# ultimate_Co-Op_v1_2.net
KiCad netlist of a schematic drawn in EAGLE
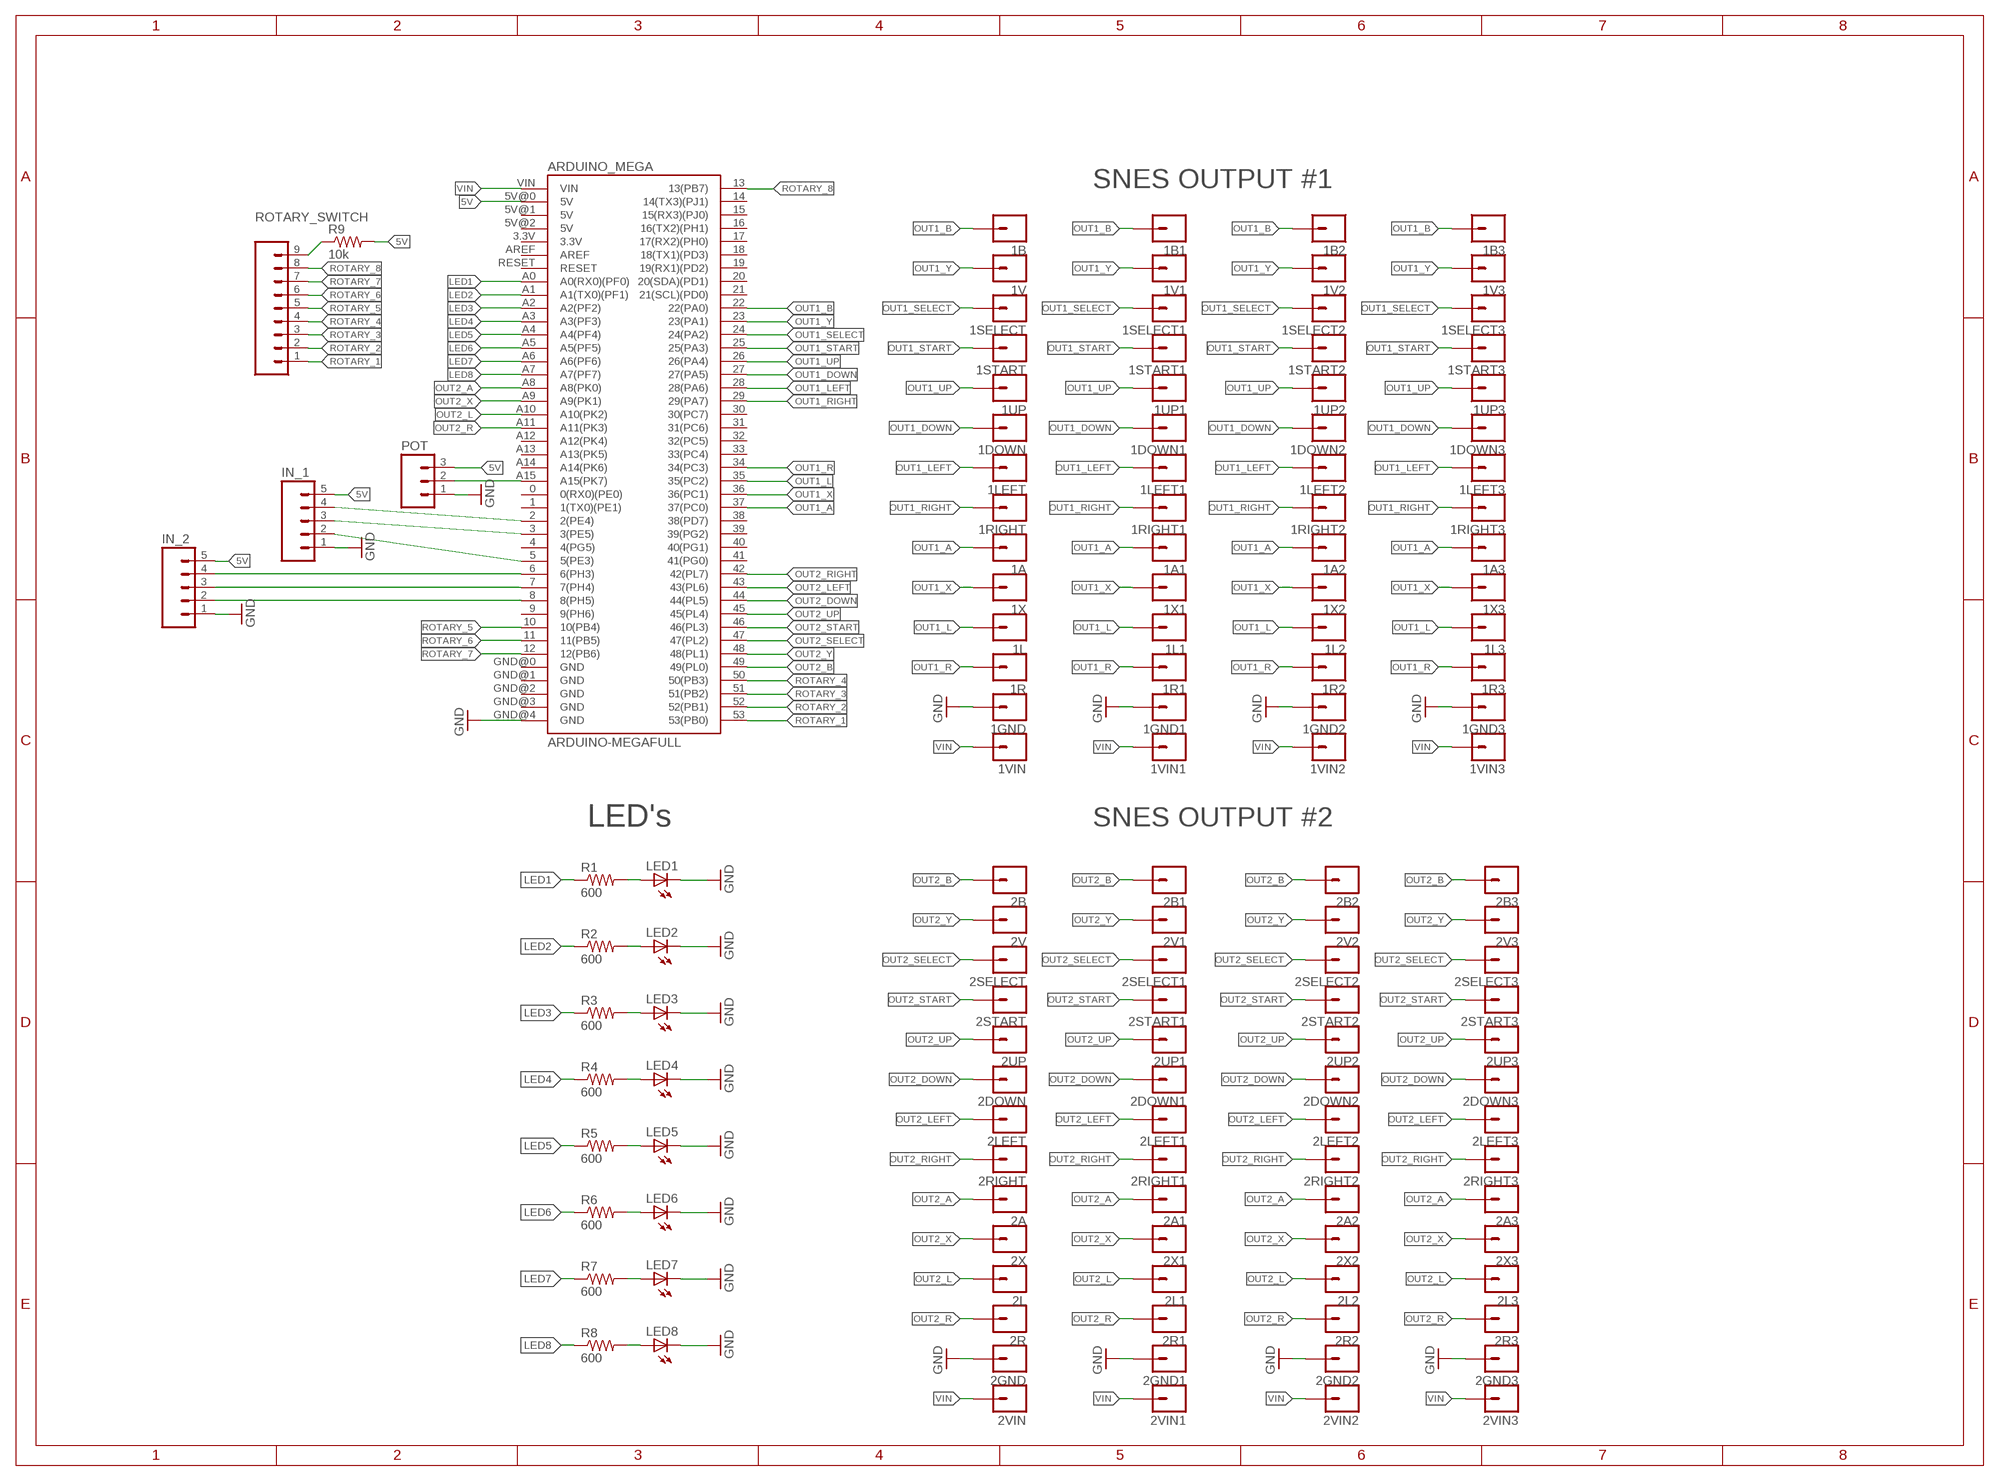
[diagram p0: schematic, sheet 1]

(export (version "E")
  (design (tool "Eeschema 10.0.6"))
  (components
    (comp (ref "1A")
      (value "M01PTH")
      (footprint "eagle-import:1X01")
      (libsource (lib "eagle-import") (part "M01PTH"))
    )
    (comp (ref "1A1")
      (value "M01PTH")
      (footprint "eagle-import:1X01")
      (libsource (lib "eagle-import") (part "M01PTH"))
    )
    (comp (ref "1A2")
      (value "M01PTH")
      (footprint "eagle-import:1X01")
      (libsource (lib "eagle-import") (part "M01PTH"))
    )
    (comp (ref "1A3")
      (value "M01PTH")
      (footprint "eagle-import:1X01")
      (libsource (lib "eagle-import") (part "M01PTH"))
    )
    (comp (ref "1B")
      (value "M01PTH")
      (footprint "eagle-import:1X01")
      (libsource (lib "eagle-import") (part "M01PTH"))
    )
    (comp (ref "1B1")
      (value "M01PTH")
      (footprint "eagle-import:1X01")
      (libsource (lib "eagle-import") (part "M01PTH"))
    )
    (comp (ref "1B2")
      (value "M01PTH")
      (footprint "eagle-import:1X01")
      (libsource (lib "eagle-import") (part "M01PTH"))
    )
    (comp (ref "1B3")
      (value "M01PTH")
      (footprint "eagle-import:1X01")
      (libsource (lib "eagle-import") (part "M01PTH"))
    )
    (comp (ref "1DOWN")
      (value "M01PTH")
      (footprint "eagle-import:1X01")
      (libsource (lib "eagle-import") (part "M01PTH"))
    )
    (comp (ref "1DOWN1")
      (value "M01PTH")
      (footprint "eagle-import:1X01")
      (libsource (lib "eagle-import") (part "M01PTH"))
    )
    (comp (ref "1DOWN2")
      (value "M01PTH")
      (footprint "eagle-import:1X01")
      (libsource (lib "eagle-import") (part "M01PTH"))
    )
    (comp (ref "1DOWN3")
      (value "M01PTH")
      (footprint "eagle-import:1X01")
      (libsource (lib "eagle-import") (part "M01PTH"))
    )
    (comp (ref "1GND")
      (value "M01PTH")
      (footprint "eagle-import:1X01")
      (libsource (lib "eagle-import") (part "M01PTH"))
    )
    (comp (ref "1GND1")
      (value "M01PTH")
      (footprint "eagle-import:1X01")
      (libsource (lib "eagle-import") (part "M01PTH"))
    )
    (comp (ref "1GND2")
      (value "M01PTH")
      (footprint "eagle-import:1X01")
      (libsource (lib "eagle-import") (part "M01PTH"))
    )
    (comp (ref "1GND3")
      (value "M01PTH")
      (footprint "eagle-import:1X01")
      (libsource (lib "eagle-import") (part "M01PTH"))
    )
    (comp (ref "1L")
      (value "M01PTH")
      (footprint "eagle-import:1X01")
      (libsource (lib "eagle-import") (part "M01PTH"))
    )
    (comp (ref "1L1")
      (value "M01PTH")
      (footprint "eagle-import:1X01")
      (libsource (lib "eagle-import") (part "M01PTH"))
    )
    (comp (ref "1L2")
      (value "M01PTH")
      (footprint "eagle-import:1X01")
      (libsource (lib "eagle-import") (part "M01PTH"))
    )
    (comp (ref "1L3")
      (value "M01PTH")
      (footprint "eagle-import:1X01")
      (libsource (lib "eagle-import") (part "M01PTH"))
    )
    (comp (ref "1LEFT")
      (value "M01PTH")
      (footprint "eagle-import:1X01")
      (libsource (lib "eagle-import") (part "M01PTH"))
    )
    (comp (ref "1LEFT1")
      (value "M01PTH")
      (footprint "eagle-import:1X01")
      (libsource (lib "eagle-import") (part "M01PTH"))
    )
    (comp (ref "1LEFT2")
      (value "M01PTH")
      (footprint "eagle-import:1X01")
      (libsource (lib "eagle-import") (part "M01PTH"))
    )
    (comp (ref "1LEFT3")
      (value "M01PTH")
      (footprint "eagle-import:1X01")
      (libsource (lib "eagle-import") (part "M01PTH"))
    )
    (comp (ref "1R")
      (value "M01PTH")
      (footprint "eagle-import:1X01")
      (libsource (lib "eagle-import") (part "M01PTH"))
    )
    (comp (ref "1R1")
      (value "M01PTH")
      (footprint "eagle-import:1X01")
      (libsource (lib "eagle-import") (part "M01PTH"))
    )
    (comp (ref "1R2")
      (value "M01PTH")
      (footprint "eagle-import:1X01")
      (libsource (lib "eagle-import") (part "M01PTH"))
    )
    (comp (ref "1R3")
      (value "M01PTH")
      (footprint "eagle-import:1X01")
      (libsource (lib "eagle-import") (part "M01PTH"))
    )
    (comp (ref "1RIGHT")
      (value "M01PTH")
      (footprint "eagle-import:1X01")
      (libsource (lib "eagle-import") (part "M01PTH"))
    )
    (comp (ref "1RIGHT1")
      (value "M01PTH")
      (footprint "eagle-import:1X01")
      (libsource (lib "eagle-import") (part "M01PTH"))
    )
    (comp (ref "1RIGHT2")
      (value "M01PTH")
      (footprint "eagle-import:1X01")
      (libsource (lib "eagle-import") (part "M01PTH"))
    )
    (comp (ref "1RIGHT3")
      (value "M01PTH")
      (footprint "eagle-import:1X01")
      (libsource (lib "eagle-import") (part "M01PTH"))
    )
    (comp (ref "1SELECT")
      (value "M01PTH")
      (footprint "eagle-import:1X01")
      (libsource (lib "eagle-import") (part "M01PTH"))
    )
    (comp (ref "1SELECT1")
      (value "M01PTH")
      (footprint "eagle-import:1X01")
      (libsource (lib "eagle-import") (part "M01PTH"))
    )
    (comp (ref "1SELECT2")
      (value "M01PTH")
      (footprint "eagle-import:1X01")
      (libsource (lib "eagle-import") (part "M01PTH"))
    )
    (comp (ref "1SELECT3")
      (value "M01PTH")
      (footprint "eagle-import:1X01")
      (libsource (lib "eagle-import") (part "M01PTH"))
    )
    (comp (ref "1START")
      (value "M01PTH")
      (footprint "eagle-import:1X01")
      (libsource (lib "eagle-import") (part "M01PTH"))
    )
    (comp (ref "1START1")
      (value "M01PTH")
      (footprint "eagle-import:1X01")
      (libsource (lib "eagle-import") (part "M01PTH"))
    )
    (comp (ref "1START2")
      (value "M01PTH")
      (footprint "eagle-import:1X01")
      (libsource (lib "eagle-import") (part "M01PTH"))
    )
    (comp (ref "1START3")
      (value "M01PTH")
      (footprint "eagle-import:1X01")
      (libsource (lib "eagle-import") (part "M01PTH"))
    )
    (comp (ref "1UP")
      (value "M01PTH")
      (footprint "eagle-import:1X01")
      (libsource (lib "eagle-import") (part "M01PTH"))
    )
    (comp (ref "1UP1")
      (value "M01PTH")
      (footprint "eagle-import:1X01")
      (libsource (lib "eagle-import") (part "M01PTH"))
    )
    (comp (ref "1UP2")
      (value "M01PTH")
      (footprint "eagle-import:1X01")
      (libsource (lib "eagle-import") (part "M01PTH"))
    )
    (comp (ref "1UP3")
      (value "M01PTH")
      (footprint "eagle-import:1X01")
      (libsource (lib "eagle-import") (part "M01PTH"))
    )
    (comp (ref "1V")
      (value "M01PTH")
      (footprint "eagle-import:1X01")
      (libsource (lib "eagle-import") (part "M01PTH"))
    )
    (comp (ref "1V1")
      (value "M01PTH")
      (footprint "eagle-import:1X01")
      (libsource (lib "eagle-import") (part "M01PTH"))
    )
    (comp (ref "1V2")
      (value "M01PTH")
      (footprint "eagle-import:1X01")
      (libsource (lib "eagle-import") (part "M01PTH"))
    )
    (comp (ref "1V3")
      (value "M01PTH")
      (footprint "eagle-import:1X01")
      (libsource (lib "eagle-import") (part "M01PTH"))
    )
    (comp (ref "1VIN")
      (value "M01PTH")
      (footprint "eagle-import:1X01")
      (libsource (lib "eagle-import") (part "M01PTH"))
    )
    (comp (ref "1VIN1")
      (value "M01PTH")
      (footprint "eagle-import:1X01")
      (libsource (lib "eagle-import") (part "M01PTH"))
    )
    (comp (ref "1VIN2")
      (value "M01PTH")
      (footprint "eagle-import:1X01")
      (libsource (lib "eagle-import") (part "M01PTH"))
    )
    (comp (ref "1VIN3")
      (value "M01PTH")
      (footprint "eagle-import:1X01")
      (libsource (lib "eagle-import") (part "M01PTH"))
    )
    (comp (ref "1X")
      (value "M01PTH")
      (footprint "eagle-import:1X01")
      (libsource (lib "eagle-import") (part "M01PTH"))
    )
    (comp (ref "1X1")
      (value "M01PTH")
      (footprint "eagle-import:1X01")
      (libsource (lib "eagle-import") (part "M01PTH"))
    )
    (comp (ref "1X2")
      (value "M01PTH")
      (footprint "eagle-import:1X01")
      (libsource (lib "eagle-import") (part "M01PTH"))
    )
    (comp (ref "1X3")
      (value "M01PTH")
      (footprint "eagle-import:1X01")
      (libsource (lib "eagle-import") (part "M01PTH"))
    )
    (comp (ref "2A")
      (value "M01PTH")
      (footprint "eagle-import:1X01")
      (libsource (lib "eagle-import") (part "M01PTH"))
    )
    (comp (ref "2A1")
      (value "M01PTH")
      (footprint "eagle-import:1X01")
      (libsource (lib "eagle-import") (part "M01PTH"))
    )
    (comp (ref "2A2")
      (value "M01PTH")
      (footprint "eagle-import:1X01")
      (libsource (lib "eagle-import") (part "M01PTH"))
    )
    (comp (ref "2A3")
      (value "M01PTH")
      (footprint "eagle-import:1X01")
      (libsource (lib "eagle-import") (part "M01PTH"))
    )
    (comp (ref "2B")
      (value "M01PTH")
      (footprint "eagle-import:1X01")
      (libsource (lib "eagle-import") (part "M01PTH"))
    )
    (comp (ref "2B1")
      (value "M01PTH")
      (footprint "eagle-import:1X01")
      (libsource (lib "eagle-import") (part "M01PTH"))
    )
    (comp (ref "2B2")
      (value "M01PTH")
      (footprint "eagle-import:1X01")
      (libsource (lib "eagle-import") (part "M01PTH"))
    )
    (comp (ref "2B3")
      (value "M01PTH")
      (footprint "eagle-import:1X01")
      (libsource (lib "eagle-import") (part "M01PTH"))
    )
    (comp (ref "2DOWN")
      (value "M01PTH")
      (footprint "eagle-import:1X01")
      (libsource (lib "eagle-import") (part "M01PTH"))
    )
    (comp (ref "2DOWN1")
      (value "M01PTH")
      (footprint "eagle-import:1X01")
      (libsource (lib "eagle-import") (part "M01PTH"))
    )
    (comp (ref "2DOWN2")
      (value "M01PTH")
      (footprint "eagle-import:1X01")
      (libsource (lib "eagle-import") (part "M01PTH"))
    )
    (comp (ref "2DOWN3")
      (value "M01PTH")
      (footprint "eagle-import:1X01")
      (libsource (lib "eagle-import") (part "M01PTH"))
    )
    (comp (ref "2GND")
      (value "M01PTH")
      (footprint "eagle-import:1X01")
      (libsource (lib "eagle-import") (part "M01PTH"))
    )
    (comp (ref "2GND1")
      (value "M01PTH")
      (footprint "eagle-import:1X01")
      (libsource (lib "eagle-import") (part "M01PTH"))
    )
    (comp (ref "2GND2")
      (value "M01PTH")
      (footprint "eagle-import:1X01")
      (libsource (lib "eagle-import") (part "M01PTH"))
    )
    (comp (ref "2GND3")
      (value "M01PTH")
      (footprint "eagle-import:1X01")
      (libsource (lib "eagle-import") (part "M01PTH"))
    )
    (comp (ref "2L")
      (value "M01PTH")
      (footprint "eagle-import:1X01")
      (libsource (lib "eagle-import") (part "M01PTH"))
    )
    (comp (ref "2L1")
      (value "M01PTH")
      (footprint "eagle-import:1X01")
      (libsource (lib "eagle-import") (part "M01PTH"))
    )
    (comp (ref "2L2")
      (value "M01PTH")
      (footprint "eagle-import:1X01")
      (libsource (lib "eagle-import") (part "M01PTH"))
    )
    (comp (ref "2L3")
      (value "M01PTH")
      (footprint "eagle-import:1X01")
      (libsource (lib "eagle-import") (part "M01PTH"))
    )
    (comp (ref "2LEFT")
      (value "M01PTH")
      (footprint "eagle-import:1X01")
      (libsource (lib "eagle-import") (part "M01PTH"))
    )
    (comp (ref "2LEFT1")
      (value "M01PTH")
      (footprint "eagle-import:1X01")
      (libsource (lib "eagle-import") (part "M01PTH"))
    )
    (comp (ref "2LEFT2")
      (value "M01PTH")
      (footprint "eagle-import:1X01")
      (libsource (lib "eagle-import") (part "M01PTH"))
    )
    (comp (ref "2LEFT3")
      (value "M01PTH")
      (footprint "eagle-import:1X01")
      (libsource (lib "eagle-import") (part "M01PTH"))
    )
    (comp (ref "2R")
      (value "M01PTH")
      (footprint "eagle-import:1X01")
      (libsource (lib "eagle-import") (part "M01PTH"))
    )
    (comp (ref "2R1")
      (value "M01PTH")
      (footprint "eagle-import:1X01")
      (libsource (lib "eagle-import") (part "M01PTH"))
    )
    (comp (ref "2R2")
      (value "M01PTH")
      (footprint "eagle-import:1X01")
      (libsource (lib "eagle-import") (part "M01PTH"))
    )
    (comp (ref "2R3")
      (value "M01PTH")
      (footprint "eagle-import:1X01")
      (libsource (lib "eagle-import") (part "M01PTH"))
    )
    (comp (ref "2RIGHT")
      (value "M01PTH")
      (footprint "eagle-import:1X01")
      (libsource (lib "eagle-import") (part "M01PTH"))
    )
    (comp (ref "2RIGHT1")
      (value "M01PTH")
      (footprint "eagle-import:1X01")
      (libsource (lib "eagle-import") (part "M01PTH"))
    )
    (comp (ref "2RIGHT2")
      (value "M01PTH")
      (footprint "eagle-import:1X01")
      (libsource (lib "eagle-import") (part "M01PTH"))
    )
    (comp (ref "2RIGHT3")
      (value "M01PTH")
      (footprint "eagle-import:1X01")
      (libsource (lib "eagle-import") (part "M01PTH"))
    )
    (comp (ref "2SELECT")
      (value "M01PTH")
      (footprint "eagle-import:1X01")
      (libsource (lib "eagle-import") (part "M01PTH"))
    )
    (comp (ref "2SELECT1")
      (value "M01PTH")
      (footprint "eagle-import:1X01")
      (libsource (lib "eagle-import") (part "M01PTH"))
    )
    (comp (ref "2SELECT2")
      (value "M01PTH")
      (footprint "eagle-import:1X01")
      (libsource (lib "eagle-import") (part "M01PTH"))
    )
    (comp (ref "2SELECT3")
      (value "M01PTH")
      (footprint "eagle-import:1X01")
      (libsource (lib "eagle-import") (part "M01PTH"))
    )
    (comp (ref "2START")
      (value "M01PTH")
      (footprint "eagle-import:1X01")
      (libsource (lib "eagle-import") (part "M01PTH"))
    )
    (comp (ref "2START1")
      (value "M01PTH")
      (footprint "eagle-import:1X01")
      (libsource (lib "eagle-import") (part "M01PTH"))
    )
    (comp (ref "2START2")
      (value "M01PTH")
      (footprint "eagle-import:1X01")
      (libsource (lib "eagle-import") (part "M01PTH"))
    )
    (comp (ref "2START3")
      (value "M01PTH")
      (footprint "eagle-import:1X01")
      (libsource (lib "eagle-import") (part "M01PTH"))
    )
    (comp (ref "2UP")
      (value "M01PTH")
      (footprint "eagle-import:1X01")
      (libsource (lib "eagle-import") (part "M01PTH"))
    )
    (comp (ref "2UP1")
      (value "M01PTH")
      (footprint "eagle-import:1X01")
      (libsource (lib "eagle-import") (part "M01PTH"))
    )
    (comp (ref "2UP2")
      (value "M01PTH")
      (footprint "eagle-import:1X01")
      (libsource (lib "eagle-import") (part "M01PTH"))
    )
    (comp (ref "2UP3")
      (value "M01PTH")
      (footprint "eagle-import:1X01")
      (libsource (lib "eagle-import") (part "M01PTH"))
    )
    (comp (ref "2V")
      (value "M01PTH")
      (footprint "eagle-import:1X01")
      (libsource (lib "eagle-import") (part "M01PTH"))
    )
    (comp (ref "2V1")
      (value "M01PTH")
      (footprint "eagle-import:1X01")
      (libsource (lib "eagle-import") (part "M01PTH"))
    )
    (comp (ref "2V2")
      (value "M01PTH")
      (footprint "eagle-import:1X01")
      (libsource (lib "eagle-import") (part "M01PTH"))
    )
    (comp (ref "2V3")
      (value "M01PTH")
      (footprint "eagle-import:1X01")
      (libsource (lib "eagle-import") (part "M01PTH"))
    )
    (comp (ref "2VIN")
      (value "M01PTH")
      (footprint "eagle-import:1X01")
      (libsource (lib "eagle-import") (part "M01PTH"))
    )
    (comp (ref "2VIN1")
      (value "M01PTH")
      (footprint "eagle-import:1X01")
      (libsource (lib "eagle-import") (part "M01PTH"))
    )
    (comp (ref "2VIN2")
      (value "M01PTH")
      (footprint "eagle-import:1X01")
      (libsource (lib "eagle-import") (part "M01PTH"))
    )
    (comp (ref "2VIN3")
      (value "M01PTH")
      (footprint "eagle-import:1X01")
      (libsource (lib "eagle-import") (part "M01PTH"))
    )
    (comp (ref "2X")
      (value "M01PTH")
      (footprint "eagle-import:1X01")
      (libsource (lib "eagle-import") (part "M01PTH"))
    )
    (comp (ref "2X1")
      (value "M01PTH")
      (footprint "eagle-import:1X01")
      (libsource (lib "eagle-import") (part "M01PTH"))
    )
    (comp (ref "2X2")
      (value "M01PTH")
      (footprint "eagle-import:1X01")
      (libsource (lib "eagle-import") (part "M01PTH"))
    )
    (comp (ref "2X3")
      (value "M01PTH")
      (footprint "eagle-import:1X01")
      (libsource (lib "eagle-import") (part "M01PTH"))
    )
    (comp (ref "ARDUINO_MEGA")
      (value "ARDUINO-MEGAFULL")
      (footprint "eagle-import:ARDUINO_MEGA")
      (libsource (lib "eagle-import") (part "ARDUINO-MEGAFULL"))
    )
    (comp (ref "IN_1")
      (value "M05PTH")
      (footprint "eagle-import:1X05")
      (libsource (lib "eagle-import") (part "M05PTH"))
    )
    (comp (ref "IN_2")
      (value "M05PTH")
      (footprint "eagle-import:1X05")
      (libsource (lib "eagle-import") (part "M05PTH"))
    )
    (comp (ref "LED1")
      (value "LED5MM")
      (footprint "eagle-import:LED5MM")
      (libsource (lib "eagle-import") (part "LED5MM"))
    )
    (comp (ref "LED2")
      (value "LED5MM")
      (footprint "eagle-import:LED5MM")
      (libsource (lib "eagle-import") (part "LED5MM"))
    )
    (comp (ref "LED3")
      (value "LED5MM")
      (footprint "eagle-import:LED5MM")
      (libsource (lib "eagle-import") (part "LED5MM"))
    )
    (comp (ref "LED4")
      (value "LED5MM")
      (footprint "eagle-import:LED5MM")
      (libsource (lib "eagle-import") (part "LED5MM"))
    )
    (comp (ref "LED5")
      (value "LED5MM")
      (footprint "eagle-import:LED5MM")
      (libsource (lib "eagle-import") (part "LED5MM"))
    )
    (comp (ref "LED6")
      (value "LED5MM")
      (footprint "eagle-import:LED5MM")
      (libsource (lib "eagle-import") (part "LED5MM"))
    )
    (comp (ref "LED7")
      (value "LED5MM")
      (footprint "eagle-import:LED5MM")
      (libsource (lib "eagle-import") (part "LED5MM"))
    )
    (comp (ref "LED8")
      (value "LED5MM")
      (footprint "eagle-import:LED5MM")
      (libsource (lib "eagle-import") (part "LED5MM"))
    )
    (comp (ref "POT")
      (value "M03LONGPADS")
      (footprint "eagle-import:1X03_LONGPADS")
      (libsource (lib "eagle-import") (part "M03LONGPADS"))
    )
    (comp (ref "R1")
      (value "600")
      (footprint "eagle-import:0204_7")
      (libsource (lib "eagle-import") (part "R-US_0204/7"))
    )
    (comp (ref "R2")
      (value "600")
      (footprint "eagle-import:0204_7")
      (libsource (lib "eagle-import") (part "R-US_0204/7"))
    )
    (comp (ref "R3")
      (value "600")
      (footprint "eagle-import:0204_7")
      (libsource (lib "eagle-import") (part "R-US_0204/7"))
    )
    (comp (ref "R4")
      (value "600")
      (footprint "eagle-import:0204_7")
      (libsource (lib "eagle-import") (part "R-US_0204/7"))
    )
    (comp (ref "R5")
      (value "600")
      (footprint "eagle-import:0204_7")
      (libsource (lib "eagle-import") (part "R-US_0204/7"))
    )
    (comp (ref "R6")
      (value "600")
      (footprint "eagle-import:0204_7")
      (libsource (lib "eagle-import") (part "R-US_0204/7"))
    )
    (comp (ref "R7")
      (value "600")
      (footprint "eagle-import:0204_7")
      (libsource (lib "eagle-import") (part "R-US_0204/7"))
    )
    (comp (ref "R8")
      (value "600")
      (footprint "eagle-import:0204_7")
      (libsource (lib "eagle-import") (part "R-US_0204/7"))
    )
    (comp (ref "R9")
      (value "10k")
      (footprint "eagle-import:0204_7")
      (libsource (lib "eagle-import") (part "R-US_0204/7"))
    )
    (comp (ref "ROTARY_SWITCH")
      (value "M09")
      (footprint "eagle-import:1X09")
      (libsource (lib "eagle-import") (part "M09"))
    )
  )
  (nets
    (net (code "1") (name "5V") (class "Default")
      (node (ref "ARDUINO_MEGA") (pin "5V@0") (pinfunction "5V_5V@0") (pintype "bidirectional"))
      (node (ref "IN_1") (pin "5") (pinfunction "5_5") (pintype "passive"))
      (node (ref "IN_2") (pin "5") (pinfunction "5_5") (pintype "passive"))
      (node (ref "POT") (pin "3") (pinfunction "3_3") (pintype "passive"))
      (node (ref "R9") (pin "2") (pinfunction "2_2") (pintype "passive"))
    )
    (net (code "2") (name "GND") (class "Default")
      (node (ref "1GND") (pin "1") (pinfunction "1_1") (pintype "passive"))
      (node (ref "1GND1") (pin "1") (pinfunction "1_1") (pintype "passive"))
      (node (ref "1GND2") (pin "1") (pinfunction "1_1") (pintype "passive"))
      (node (ref "1GND3") (pin "1") (pinfunction "1_1") (pintype "passive"))
      (node (ref "2GND") (pin "1") (pinfunction "1_1") (pintype "passive"))
      (node (ref "2GND1") (pin "1") (pinfunction "1_1") (pintype "passive"))
      (node (ref "2GND2") (pin "1") (pinfunction "1_1") (pintype "passive"))
      (node (ref "2GND3") (pin "1") (pinfunction "1_1") (pintype "passive"))
      (node (ref "ARDUINO_MEGA") (pin "GND@4") (pinfunction "GND_GND@4") (pintype "bidirectional"))
      (node (ref "IN_1") (pin "1") (pinfunction "1_1") (pintype "passive"))
      (node (ref "IN_2") (pin "1") (pinfunction "1_1") (pintype "passive"))
      (node (ref "LED1") (pin "K") (pinfunction "C_K") (pintype "passive"))
      (node (ref "LED2") (pin "K") (pinfunction "C_K") (pintype "passive"))
      (node (ref "LED3") (pin "K") (pinfunction "C_K") (pintype "passive"))
      (node (ref "LED4") (pin "K") (pinfunction "C_K") (pintype "passive"))
      (node (ref "LED5") (pin "K") (pinfunction "C_K") (pintype "passive"))
      (node (ref "LED6") (pin "K") (pinfunction "C_K") (pintype "passive"))
      (node (ref "LED7") (pin "K") (pinfunction "C_K") (pintype "passive"))
      (node (ref "LED8") (pin "K") (pinfunction "C_K") (pintype "passive"))
      (node (ref "POT") (pin "1") (pinfunction "1_1") (pintype "passive"))
    )
    (net (code "3") (name "LED1") (class "Default")
      (node (ref "ARDUINO_MEGA") (pin "A0") (pinfunction "A0(RX0)(PF0)_A0") (pintype "bidirectional"))
      (node (ref "R1") (pin "1") (pinfunction "1_1") (pintype "passive"))
    )
    (net (code "4") (name "LED2") (class "Default")
      (node (ref "ARDUINO_MEGA") (pin "A1") (pinfunction "A1(TX0)(PF1)_A1") (pintype "bidirectional"))
      (node (ref "R2") (pin "1") (pinfunction "1_1") (pintype "passive"))
    )
    (net (code "5") (name "LED3") (class "Default")
      (node (ref "ARDUINO_MEGA") (pin "A2") (pinfunction "A2(PF2)_A2") (pintype "bidirectional"))
      (node (ref "R3") (pin "1") (pinfunction "1_1") (pintype "passive"))
    )
    (net (code "6") (name "LED4") (class "Default")
      (node (ref "ARDUINO_MEGA") (pin "A3") (pinfunction "A3(PF3)_A3") (pintype "bidirectional"))
      (node (ref "R4") (pin "1") (pinfunction "1_1") (pintype "passive"))
    )
    (net (code "7") (name "LED5") (class "Default")
      (node (ref "ARDUINO_MEGA") (pin "A4") (pinfunction "A4(PF4)_A4") (pintype "bidirectional"))
      (node (ref "R5") (pin "1") (pinfunction "1_1") (pintype "passive"))
    )
    (net (code "8") (name "LED6") (class "Default")
      (node (ref "ARDUINO_MEGA") (pin "A5") (pinfunction "A5(PF5)_A5") (pintype "bidirectional"))
      (node (ref "R6") (pin "1") (pinfunction "1_1") (pintype "passive"))
    )
    (net (code "9") (name "LED7") (class "Default")
      (node (ref "ARDUINO_MEGA") (pin "A6") (pinfunction "A6(PF6)_A6") (pintype "bidirectional"))
      (node (ref "R7") (pin "1") (pinfunction "1_1") (pintype "passive"))
    )
    (net (code "10") (name "LED8") (class "Default")
      (node (ref "ARDUINO_MEGA") (pin "A7") (pinfunction "A7(PF7)_A7") (pintype "bidirectional"))
      (node (ref "R8") (pin "1") (pinfunction "1_1") (pintype "passive"))
    )
    (net (code "11") (name "Net-(ARDUINO_MEGA-2(PE4))") (class "Default")
      (node (ref "ARDUINO_MEGA") (pin "2") (pinfunction "2(PE4)_2") (pintype "bidirectional"))
      (node (ref "IN_1") (pin "4") (pinfunction "4_4") (pintype "passive"))
    )
    (net (code "12") (name "Net-(ARDUINO_MEGA-3(PE5))") (class "Default")
      (node (ref "ARDUINO_MEGA") (pin "3") (pinfunction "3(PE5)_3") (pintype "bidirectional"))
      (node (ref "IN_1") (pin "3") (pinfunction "3_3") (pintype "passive"))
    )
    (net (code "13") (name "Net-(ARDUINO_MEGA-5(PE3))") (class "Default")
      (node (ref "ARDUINO_MEGA") (pin "5") (pinfunction "5(PE3)_5") (pintype "bidirectional"))
      (node (ref "IN_1") (pin "2") (pinfunction "2_2") (pintype "passive"))
    )
    (net (code "14") (name "Net-(ARDUINO_MEGA-6(PH3))") (class "Default")
      (node (ref "ARDUINO_MEGA") (pin "6") (pinfunction "6(PH3)_6") (pintype "bidirectional"))
      (node (ref "IN_2") (pin "4") (pinfunction "4_4") (pintype "passive"))
    )
    (net (code "15") (name "Net-(ARDUINO_MEGA-7(PH4))") (class "Default")
      (node (ref "ARDUINO_MEGA") (pin "7") (pinfunction "7(PH4)_7") (pintype "bidirectional"))
      (node (ref "IN_2") (pin "3") (pinfunction "3_3") (pintype "passive"))
    )
    (net (code "16") (name "Net-(ARDUINO_MEGA-8(PH5))") (class "Default")
      (node (ref "ARDUINO_MEGA") (pin "8") (pinfunction "8(PH5)_8") (pintype "bidirectional"))
      (node (ref "IN_2") (pin "2") (pinfunction "2_2") (pintype "passive"))
    )
    (net (code "17") (name "Net-(ARDUINO_MEGA-A15(PK7))") (class "Default")
      (node (ref "ARDUINO_MEGA") (pin "A15") (pinfunction "A15(PK7)_A15") (pintype "bidirectional"))
      (node (ref "POT") (pin "2") (pinfunction "2_2") (pintype "passive"))
    )
    (net (code "18") (name "Net-(LED1-PadA)") (class "Default")
      (node (ref "LED1") (pin "A") (pinfunction "A_A") (pintype "passive"))
      (node (ref "R1") (pin "2") (pinfunction "2_2") (pintype "passive"))
    )
    (net (code "19") (name "Net-(LED2-PadA)") (class "Default")
      (node (ref "LED2") (pin "A") (pinfunction "A_A") (pintype "passive"))
      (node (ref "R2") (pin "2") (pinfunction "2_2") (pintype "passive"))
    )
    (net (code "20") (name "Net-(LED3-PadA)") (class "Default")
      (node (ref "LED3") (pin "A") (pinfunction "A_A") (pintype "passive"))
      (node (ref "R3") (pin "2") (pinfunction "2_2") (pintype "passive"))
    )
    (net (code "21") (name "Net-(LED4-PadA)") (class "Default")
      (node (ref "LED4") (pin "A") (pinfunction "A_A") (pintype "passive"))
      (node (ref "R4") (pin "2") (pinfunction "2_2") (pintype "passive"))
    )
    (net (code "22") (name "Net-(LED5-PadA)") (class "Default")
      (node (ref "LED5") (pin "A") (pinfunction "A_A") (pintype "passive"))
      (node (ref "R5") (pin "2") (pinfunction "2_2") (pintype "passive"))
    )
    (net (code "23") (name "Net-(LED6-PadA)") (class "Default")
      (node (ref "LED6") (pin "A") (pinfunction "A_A") (pintype "passive"))
      (node (ref "R6") (pin "2") (pinfunction "2_2") (pintype "passive"))
    )
    (net (code "24") (name "Net-(LED7-PadA)") (class "Default")
      (node (ref "LED7") (pin "A") (pinfunction "A_A") (pintype "passive"))
      (node (ref "R7") (pin "2") (pinfunction "2_2") (pintype "passive"))
    )
    (net (code "25") (name "Net-(LED8-PadA)") (class "Default")
      (node (ref "LED8") (pin "A") (pinfunction "A_A") (pintype "passive"))
      (node (ref "R8") (pin "2") (pinfunction "2_2") (pintype "passive"))
    )
    (net (code "26") (name "Net-(R9-Pad1)") (class "Default")
      (node (ref "R9") (pin "1") (pinfunction "1_1") (pintype "passive"))
      (node (ref "ROTARY_SWITCH") (pin "9") (pinfunction "9_9") (pintype "passive"))
    )
    (net (code "27") (name "OUT1_A") (class "Default")
      (node (ref "1A") (pin "1") (pinfunction "1_1") (pintype "passive"))
      (node (ref "1A1") (pin "1") (pinfunction "1_1") (pintype "passive"))
      (node (ref "1A2") (pin "1") (pinfunction "1_1") (pintype "passive"))
      (node (ref "1A3") (pin "1") (pinfunction "1_1") (pintype "passive"))
      (node (ref "ARDUINO_MEGA") (pin "37") (pinfunction "37(PC0)_37") (pintype "bidirectional"))
    )
    (net (code "28") (name "OUT1_B") (class "Default")
      (node (ref "1B") (pin "1") (pinfunction "1_1") (pintype "passive"))
      (node (ref "1B1") (pin "1") (pinfunction "1_1") (pintype "passive"))
      (node (ref "1B2") (pin "1") (pinfunction "1_1") (pintype "passive"))
      (node (ref "1B3") (pin "1") (pinfunction "1_1") (pintype "passive"))
      (node (ref "ARDUINO_MEGA") (pin "22") (pinfunction "22(PA0)_22") (pintype "bidirectional"))
    )
    (net (code "29") (name "OUT1_DOWN") (class "Default")
      (node (ref "1DOWN") (pin "1") (pinfunction "1_1") (pintype "passive"))
      (node (ref "1DOWN1") (pin "1") (pinfunction "1_1") (pintype "passive"))
      (node (ref "1DOWN2") (pin "1") (pinfunction "1_1") (pintype "passive"))
      (node (ref "1DOWN3") (pin "1") (pinfunction "1_1") (pintype "passive"))
      (node (ref "ARDUINO_MEGA") (pin "27") (pinfunction "27(PA5)_27") (pintype "bidirectional"))
    )
    (net (code "30") (name "OUT1_L") (class "Default")
      (node (ref "1L") (pin "1") (pinfunction "1_1") (pintype "passive"))
      (node (ref "1L1") (pin "1") (pinfunction "1_1") (pintype "passive"))
      (node (ref "1L2") (pin "1") (pinfunction "1_1") (pintype "passive"))
      (node (ref "1L3") (pin "1") (pinfunction "1_1") (pintype "passive"))
      (node (ref "ARDUINO_MEGA") (pin "35") (pinfunction "35(PC2)_35") (pintype "bidirectional"))
    )
    (net (code "31") (name "OUT1_LEFT") (class "Default")
      (node (ref "1LEFT") (pin "1") (pinfunction "1_1") (pintype "passive"))
      (node (ref "1LEFT1") (pin "1") (pinfunction "1_1") (pintype "passive"))
      (node (ref "1LEFT2") (pin "1") (pinfunction "1_1") (pintype "passive"))
      (node (ref "1LEFT3") (pin "1") (pinfunction "1_1") (pintype "passive"))
      (node (ref "ARDUINO_MEGA") (pin "28") (pinfunction "28(PA6)_28") (pintype "bidirectional"))
    )
    (net (code "32") (name "OUT1_R") (class "Default")
      (node (ref "1R") (pin "1") (pinfunction "1_1") (pintype "passive"))
      (node (ref "1R1") (pin "1") (pinfunction "1_1") (pintype "passive"))
      (node (ref "1R2") (pin "1") (pinfunction "1_1") (pintype "passive"))
      (node (ref "1R3") (pin "1") (pinfunction "1_1") (pintype "passive"))
      (node (ref "ARDUINO_MEGA") (pin "34") (pinfunction "34(PC3)_34") (pintype "bidirectional"))
    )
    (net (code "33") (name "OUT1_RIGHT") (class "Default")
      (node (ref "1RIGHT") (pin "1") (pinfunction "1_1") (pintype "passive"))
      (node (ref "1RIGHT1") (pin "1") (pinfunction "1_1") (pintype "passive"))
      (node (ref "1RIGHT2") (pin "1") (pinfunction "1_1") (pintype "passive"))
      (node (ref "1RIGHT3") (pin "1") (pinfunction "1_1") (pintype "passive"))
      (node (ref "ARDUINO_MEGA") (pin "29") (pinfunction "29(PA7)_29") (pintype "bidirectional"))
    )
    (net (code "34") (name "OUT1_SELECT") (class "Default")
      (node (ref "1SELECT") (pin "1") (pinfunction "1_1") (pintype "passive"))
      (node (ref "1SELECT1") (pin "1") (pinfunction "1_1") (pintype "passive"))
      (node (ref "1SELECT2") (pin "1") (pinfunction "1_1") (pintype "passive"))
      (node (ref "1SELECT3") (pin "1") (pinfunction "1_1") (pintype "passive"))
      (node (ref "ARDUINO_MEGA") (pin "24") (pinfunction "24(PA2)_24") (pintype "bidirectional"))
    )
    (net (code "35") (name "OUT1_START") (class "Default")
      (node (ref "1START") (pin "1") (pinfunction "1_1") (pintype "passive"))
      (node (ref "1START1") (pin "1") (pinfunction "1_1") (pintype "passive"))
      (node (ref "1START2") (pin "1") (pinfunction "1_1") (pintype "passive"))
      (node (ref "1START3") (pin "1") (pinfunction "1_1") (pintype "passive"))
      (node (ref "ARDUINO_MEGA") (pin "25") (pinfunction "25(PA3)_25") (pintype "bidirectional"))
    )
    (net (code "36") (name "OUT1_UP") (class "Default")
      (node (ref "1UP") (pin "1") (pinfunction "1_1") (pintype "passive"))
      (node (ref "1UP1") (pin "1") (pinfunction "1_1") (pintype "passive"))
      (node (ref "1UP2") (pin "1") (pinfunction "1_1") (pintype "passive"))
      (node (ref "1UP3") (pin "1") (pinfunction "1_1") (pintype "passive"))
      (node (ref "ARDUINO_MEGA") (pin "26") (pinfunction "26(PA4)_26") (pintype "bidirectional"))
    )
    (net (code "37") (name "OUT1_X") (class "Default")
      (node (ref "1X") (pin "1") (pinfunction "1_1") (pintype "passive"))
      (node (ref "1X1") (pin "1") (pinfunction "1_1") (pintype "passive"))
      (node (ref "1X2") (pin "1") (pinfunction "1_1") (pintype "passive"))
      (node (ref "1X3") (pin "1") (pinfunction "1_1") (pintype "passive"))
      (node (ref "ARDUINO_MEGA") (pin "36") (pinfunction "36(PC1)_36") (pintype "bidirectional"))
    )
    (net (code "38") (name "OUT1_Y") (class "Default")
      (node (ref "1V") (pin "1") (pinfunction "1_1") (pintype "passive"))
      (node (ref "1V1") (pin "1") (pinfunction "1_1") (pintype "passive"))
      (node (ref "1V2") (pin "1") (pinfunction "1_1") (pintype "passive"))
      (node (ref "1V3") (pin "1") (pinfunction "1_1") (pintype "passive"))
      (node (ref "ARDUINO_MEGA") (pin "23") (pinfunction "23(PA1)_23") (pintype "bidirectional"))
    )
    (net (code "39") (name "OUT2_A") (class "Default")
      (node (ref "2A") (pin "1") (pinfunction "1_1") (pintype "passive"))
      (node (ref "2A1") (pin "1") (pinfunction "1_1") (pintype "passive"))
      (node (ref "2A2") (pin "1") (pinfunction "1_1") (pintype "passive"))
      (node (ref "2A3") (pin "1") (pinfunction "1_1") (pintype "passive"))
      (node (ref "ARDUINO_MEGA") (pin "A8") (pinfunction "A8(PK0)_A8") (pintype "bidirectional"))
    )
    (net (code "40") (name "OUT2_B") (class "Default")
      (node (ref "2B") (pin "1") (pinfunction "1_1") (pintype "passive"))
      (node (ref "2B1") (pin "1") (pinfunction "1_1") (pintype "passive"))
      (node (ref "2B2") (pin "1") (pinfunction "1_1") (pintype "passive"))
      (node (ref "2B3") (pin "1") (pinfunction "1_1") (pintype "passive"))
      (node (ref "ARDUINO_MEGA") (pin "49") (pinfunction "49(PL0)_49") (pintype "bidirectional"))
    )
    (net (code "41") (name "OUT2_DOWN") (class "Default")
      (node (ref "2DOWN") (pin "1") (pinfunction "1_1") (pintype "passive"))
      (node (ref "2DOWN1") (pin "1") (pinfunction "1_1") (pintype "passive"))
      (node (ref "2DOWN2") (pin "1") (pinfunction "1_1") (pintype "passive"))
      (node (ref "2DOWN3") (pin "1") (pinfunction "1_1") (pintype "passive"))
      (node (ref "ARDUINO_MEGA") (pin "44") (pinfunction "44(PL5)_44") (pintype "bidirectional"))
    )
    (net (code "42") (name "OUT2_L") (class "Default")
      (node (ref "2L") (pin "1") (pinfunction "1_1") (pintype "passive"))
      (node (ref "2L1") (pin "1") (pinfunction "1_1") (pintype "passive"))
      (node (ref "2L2") (pin "1") (pinfunction "1_1") (pintype "passive"))
      (node (ref "2L3") (pin "1") (pinfunction "1_1") (pintype "passive"))
      (node (ref "ARDUINO_MEGA") (pin "A10") (pinfunction "A10(PK2)_A10") (pintype "bidirectional"))
    )
    (net (code "43") (name "OUT2_LEFT") (class "Default")
      (node (ref "2LEFT") (pin "1") (pinfunction "1_1") (pintype "passive"))
      (node (ref "2LEFT1") (pin "1") (pinfunction "1_1") (pintype "passive"))
      (node (ref "2LEFT2") (pin "1") (pinfunction "1_1") (pintype "passive"))
      (node (ref "2LEFT3") (pin "1") (pinfunction "1_1") (pintype "passive"))
      (node (ref "ARDUINO_MEGA") (pin "43") (pinfunction "43(PL6)_43") (pintype "bidirectional"))
    )
    (net (code "44") (name "OUT2_R") (class "Default")
      (node (ref "2R") (pin "1") (pinfunction "1_1") (pintype "passive"))
      (node (ref "2R1") (pin "1") (pinfunction "1_1") (pintype "passive"))
      (node (ref "2R2") (pin "1") (pinfunction "1_1") (pintype "passive"))
      (node (ref "2R3") (pin "1") (pinfunction "1_1") (pintype "passive"))
      (node (ref "ARDUINO_MEGA") (pin "A11") (pinfunction "A11(PK3)_A11") (pintype "bidirectional"))
    )
    (net (code "45") (name "OUT2_RIGHT") (class "Default")
      (node (ref "2RIGHT") (pin "1") (pinfunction "1_1") (pintype "passive"))
      (node (ref "2RIGHT1") (pin "1") (pinfunction "1_1") (pintype "passive"))
      (node (ref "2RIGHT2") (pin "1") (pinfunction "1_1") (pintype "passive"))
      (node (ref "2RIGHT3") (pin "1") (pinfunction "1_1") (pintype "passive"))
      (node (ref "ARDUINO_MEGA") (pin "42") (pinfunction "42(PL7)_42") (pintype "bidirectional"))
    )
    (net (code "46") (name "OUT2_SELECT") (class "Default")
      (node (ref "2SELECT") (pin "1") (pinfunction "1_1") (pintype "passive"))
      (node (ref "2SELECT1") (pin "1") (pinfunction "1_1") (pintype "passive"))
      (node (ref "2SELECT2") (pin "1") (pinfunction "1_1") (pintype "passive"))
      (node (ref "2SELECT3") (pin "1") (pinfunction "1_1") (pintype "passive"))
      (node (ref "ARDUINO_MEGA") (pin "47") (pinfunction "47(PL2)_47") (pintype "bidirectional"))
    )
    (net (code "47") (name "OUT2_START") (class "Default")
      (node (ref "2START") (pin "1") (pinfunction "1_1") (pintype "passive"))
      (node (ref "2START1") (pin "1") (pinfunction "1_1") (pintype "passive"))
      (node (ref "2START2") (pin "1") (pinfunction "1_1") (pintype "passive"))
      (node (ref "2START3") (pin "1") (pinfunction "1_1") (pintype "passive"))
      (node (ref "ARDUINO_MEGA") (pin "46") (pinfunction "46(PL3)_46") (pintype "bidirectional"))
    )
    (net (code "48") (name "OUT2_UP") (class "Default")
      (node (ref "2UP") (pin "1") (pinfunction "1_1") (pintype "passive"))
      (node (ref "2UP1") (pin "1") (pinfunction "1_1") (pintype "passive"))
      (node (ref "2UP2") (pin "1") (pinfunction "1_1") (pintype "passive"))
      (node (ref "2UP3") (pin "1") (pinfunction "1_1") (pintype "passive"))
      (node (ref "ARDUINO_MEGA") (pin "45") (pinfunction "45(PL4)_45") (pintype "bidirectional"))
    )
    (net (code "49") (name "OUT2_X") (class "Default")
      (node (ref "2X") (pin "1") (pinfunction "1_1") (pintype "passive"))
      (node (ref "2X1") (pin "1") (pinfunction "1_1") (pintype "passive"))
      (node (ref "2X2") (pin "1") (pinfunction "1_1") (pintype "passive"))
      (node (ref "2X3") (pin "1") (pinfunction "1_1") (pintype "passive"))
      (node (ref "ARDUINO_MEGA") (pin "A9") (pinfunction "A9(PK1)_A9") (pintype "bidirectional"))
    )
    (net (code "50") (name "OUT2_Y") (class "Default")
      (node (ref "2V") (pin "1") (pinfunction "1_1") (pintype "passive"))
      (node (ref "2V1") (pin "1") (pinfunction "1_1") (pintype "passive"))
      (node (ref "2V2") (pin "1") (pinfunction "1_1") (pintype "passive"))
      (node (ref "2V3") (pin "1") (pinfunction "1_1") (pintype "passive"))
      (node (ref "ARDUINO_MEGA") (pin "48") (pinfunction "48(PL1)_48") (pintype "bidirectional"))
    )
    (net (code "51") (name "ROTARY_1") (class "Default")
      (node (ref "ARDUINO_MEGA") (pin "53") (pinfunction "53(PB0)_53") (pintype "bidirectional"))
      (node (ref "ROTARY_SWITCH") (pin "1") (pinfunction "1_1") (pintype "passive"))
    )
    (net (code "52") (name "ROTARY_2") (class "Default")
      (node (ref "ARDUINO_MEGA") (pin "52") (pinfunction "52(PB1)_52") (pintype "bidirectional"))
      (node (ref "ROTARY_SWITCH") (pin "2") (pinfunction "2_2") (pintype "passive"))
    )
    (net (code "53") (name "ROTARY_3") (class "Default")
      (node (ref "ARDUINO_MEGA") (pin "51") (pinfunction "51(PB2)_51") (pintype "bidirectional"))
      (node (ref "ROTARY_SWITCH") (pin "3") (pinfunction "3_3") (pintype "passive"))
    )
    (net (code "54") (name "ROTARY_4") (class "Default")
      (node (ref "ARDUINO_MEGA") (pin "50") (pinfunction "50(PB3)_50") (pintype "bidirectional"))
      (node (ref "ROTARY_SWITCH") (pin "4") (pinfunction "4_4") (pintype "passive"))
    )
    (net (code "55") (name "ROTARY_5") (class "Default")
      (node (ref "ARDUINO_MEGA") (pin "10") (pinfunction "10(PB4)_10") (pintype "bidirectional"))
      (node (ref "ROTARY_SWITCH") (pin "5") (pinfunction "5_5") (pintype "passive"))
    )
    (net (code "56") (name "ROTARY_6") (class "Default")
      (node (ref "ARDUINO_MEGA") (pin "11") (pinfunction "11(PB5)_11") (pintype "bidirectional"))
      (node (ref "ROTARY_SWITCH") (pin "6") (pinfunction "6_6") (pintype "passive"))
    )
    (net (code "57") (name "ROTARY_7") (class "Default")
      (node (ref "ARDUINO_MEGA") (pin "12") (pinfunction "12(PB6)_12") (pintype "bidirectional"))
      (node (ref "ROTARY_SWITCH") (pin "7") (pinfunction "7_7") (pintype "passive"))
    )
    (net (code "58") (name "ROTARY_8") (class "Default")
      (node (ref "ARDUINO_MEGA") (pin "13") (pinfunction "13(PB7)_13") (pintype "bidirectional"))
      (node (ref "ROTARY_SWITCH") (pin "8") (pinfunction "8_8") (pintype "passive"))
    )
    (net (code "59") (name "VIN") (class "Default")
      (node (ref "1VIN") (pin "1") (pinfunction "1_1") (pintype "passive"))
      (node (ref "1VIN1") (pin "1") (pinfunction "1_1") (pintype "passive"))
      (node (ref "1VIN2") (pin "1") (pinfunction "1_1") (pintype "passive"))
      (node (ref "1VIN3") (pin "1") (pinfunction "1_1") (pintype "passive"))
      (node (ref "2VIN") (pin "1") (pinfunction "1_1") (pintype "passive"))
      (node (ref "2VIN1") (pin "1") (pinfunction "1_1") (pintype "passive"))
      (node (ref "2VIN2") (pin "1") (pinfunction "1_1") (pintype "passive"))
      (node (ref "2VIN3") (pin "1") (pinfunction "1_1") (pintype "passive"))
      (node (ref "ARDUINO_MEGA") (pin "VIN") (pinfunction "VIN_VIN") (pintype "bidirectional"))
    )
    (net (code "60") (name "unconnected-(ARDUINO_MEGA-0(RX0)(PE0)-Pad0)") (class "Default")
      (node (ref "ARDUINO_MEGA") (pin "0") (pinfunction "0(RX0)(PE0)_0") (pintype "bidirectional"))
    )
    (net (code "61") (name "unconnected-(ARDUINO_MEGA-1(TX0)(PE1)-Pad1)") (class "Default")
      (node (ref "ARDUINO_MEGA") (pin "1") (pinfunction "1(TX0)(PE1)_1") (pintype "bidirectional"))
    )
    (net (code "62") (name "unconnected-(ARDUINO_MEGA-4(PG5)-Pad4)") (class "Default")
      (node (ref "ARDUINO_MEGA") (pin "4") (pinfunction "4(PG5)_4") (pintype "bidirectional"))
    )
    (net (code "63") (name "unconnected-(ARDUINO_MEGA-5V-Pad5V@1)") (class "Default")
      (node (ref "ARDUINO_MEGA") (pin "5V@1") (pinfunction "5V_5V@1") (pintype "bidirectional"))
    )
    (net (code "64") (name "unconnected-(ARDUINO_MEGA-5V-Pad5V@2)") (class "Default")
      (node (ref "ARDUINO_MEGA") (pin "5V@2") (pinfunction "5V_5V@2") (pintype "bidirectional"))
    )
    (net (code "65") (name "unconnected-(ARDUINO_MEGA-9(PH6)-Pad9)") (class "Default")
      (node (ref "ARDUINO_MEGA") (pin "9") (pinfunction "9(PH6)_9") (pintype "bidirectional"))
    )
    (net (code "66") (name "unconnected-(ARDUINO_MEGA-14(TX3)(PJ1)-Pad14)") (class "Default")
      (node (ref "ARDUINO_MEGA") (pin "14") (pinfunction "14(TX3)(PJ1)_14") (pintype "bidirectional"))
    )
    (net (code "67") (name "unconnected-(ARDUINO_MEGA-15(RX3)(PJ0)-Pad15)") (class "Default")
      (node (ref "ARDUINO_MEGA") (pin "15") (pinfunction "15(RX3)(PJ0)_15") (pintype "bidirectional"))
    )
    (net (code "68") (name "unconnected-(ARDUINO_MEGA-16(TX2)(PH1)-Pad16)") (class "Default")
      (node (ref "ARDUINO_MEGA") (pin "16") (pinfunction "16(TX2)(PH1)_16") (pintype "bidirectional"))
    )
    (net (code "69") (name "unconnected-(ARDUINO_MEGA-17(RX2)(PH0)-Pad17)") (class "Default")
      (node (ref "ARDUINO_MEGA") (pin "17") (pinfunction "17(RX2)(PH0)_17") (pintype "bidirectional"))
    )
    (net (code "70") (name "unconnected-(ARDUINO_MEGA-18(TX1)(PD3)-Pad18)") (class "Default")
      (node (ref "ARDUINO_MEGA") (pin "18") (pinfunction "18(TX1)(PD3)_18") (pintype "bidirectional"))
    )
    (net (code "71") (name "unconnected-(ARDUINO_MEGA-19(RX1)(PD2)-Pad19)") (class "Default")
      (node (ref "ARDUINO_MEGA") (pin "19") (pinfunction "19(RX1)(PD2)_19") (pintype "bidirectional"))
    )
    (net (code "72") (name "unconnected-(ARDUINO_MEGA-20(SDA)(PD1)-Pad20)") (class "Default")
      (node (ref "ARDUINO_MEGA") (pin "20") (pinfunction "20(SDA)(PD1)_20") (pintype "bidirectional"))
    )
    (net (code "73") (name "unconnected-(ARDUINO_MEGA-21(SCL)(PD0)-Pad21)") (class "Default")
      (node (ref "ARDUINO_MEGA") (pin "21") (pinfunction "21(SCL)(PD0)_21") (pintype "bidirectional"))
    )
    (net (code "74") (name "unconnected-(ARDUINO_MEGA-30(PC7)-Pad30)") (class "Default")
      (node (ref "ARDUINO_MEGA") (pin "30") (pinfunction "30(PC7)_30") (pintype "bidirectional"))
    )
    (net (code "75") (name "unconnected-(ARDUINO_MEGA-31(PC6)-Pad31)") (class "Default")
      (node (ref "ARDUINO_MEGA") (pin "31") (pinfunction "31(PC6)_31") (pintype "bidirectional"))
    )
    (net (code "76") (name "unconnected-(ARDUINO_MEGA-32(PC5)-Pad32)") (class "Default")
      (node (ref "ARDUINO_MEGA") (pin "32") (pinfunction "32(PC5)_32") (pintype "bidirectional"))
    )
    (net (code "77") (name "unconnected-(ARDUINO_MEGA-33(PC4)-Pad33)") (class "Default")
      (node (ref "ARDUINO_MEGA") (pin "33") (pinfunction "33(PC4)_33") (pintype "bidirectional"))
    )
    (net (code "78") (name "unconnected-(ARDUINO_MEGA-38(PD7)-Pad38)") (class "Default")
      (node (ref "ARDUINO_MEGA") (pin "38") (pinfunction "38(PD7)_38") (pintype "bidirectional"))
    )
    (net (code "79") (name "unconnected-(ARDUINO_MEGA-39(PG2)-Pad39)") (class "Default")
      (node (ref "ARDUINO_MEGA") (pin "39") (pinfunction "39(PG2)_39") (pintype "bidirectional"))
    )
    (net (code "80") (name "unconnected-(ARDUINO_MEGA-40(PG1)-Pad40)") (class "Default")
      (node (ref "ARDUINO_MEGA") (pin "40") (pinfunction "40(PG1)_40") (pintype "bidirectional"))
    )
    (net (code "81") (name "unconnected-(ARDUINO_MEGA-41(PG0)-Pad41)") (class "Default")
      (node (ref "ARDUINO_MEGA") (pin "41") (pinfunction "41(PG0)_41") (pintype "bidirectional"))
    )
    (net (code "82") (name "unconnected-(ARDUINO_MEGA-A12(PK4)-PadA12)") (class "Default")
      (node (ref "ARDUINO_MEGA") (pin "A12") (pinfunction "A12(PK4)_A12") (pintype "bidirectional"))
    )
    (net (code "83") (name "unconnected-(ARDUINO_MEGA-A13(PK5)-PadA13)") (class "Default")
      (node (ref "ARDUINO_MEGA") (pin "A13") (pinfunction "A13(PK5)_A13") (pintype "bidirectional"))
    )
    (net (code "84") (name "unconnected-(ARDUINO_MEGA-A14(PK6)-PadA14)") (class "Default")
      (node (ref "ARDUINO_MEGA") (pin "A14") (pinfunction "A14(PK6)_A14") (pintype "bidirectional"))
    )
    (net (code "85") (name "unconnected-(ARDUINO_MEGA-GND-PadGND@0)") (class "Default")
      (node (ref "ARDUINO_MEGA") (pin "GND@0") (pinfunction "GND_GND@0") (pintype "bidirectional"))
    )
    (net (code "86") (name "unconnected-(ARDUINO_MEGA-GND-PadGND@1)") (class "Default")
      (node (ref "ARDUINO_MEGA") (pin "GND@1") (pinfunction "GND_GND@1") (pintype "bidirectional"))
    )
    (net (code "87") (name "unconnected-(ARDUINO_MEGA-GND-PadGND@2)") (class "Default")
      (node (ref "ARDUINO_MEGA") (pin "GND@2") (pinfunction "GND_GND@2") (pintype "bidirectional"))
    )
    (net (code "88") (name "unconnected-(ARDUINO_MEGA-GND-PadGND@3)") (class "Default")
      (node (ref "ARDUINO_MEGA") (pin "GND@3") (pinfunction "GND_GND@3") (pintype "bidirectional"))
    )
    (net (code "89") (name "unconnected-(ARDUINO_MEGA-Pad3.3V)") (class "Default")
      (node (ref "ARDUINO_MEGA") (pin "3.3V") (pinfunction "3.3V_3.3V") (pintype "bidirectional"))
    )
    (net (code "90") (name "unconnected-(ARDUINO_MEGA-PadAREF)") (class "Default")
      (node (ref "ARDUINO_MEGA") (pin "AREF") (pinfunction "AREF_AREF") (pintype "bidirectional"))
    )
    (net (code "91") (name "unconnected-(ARDUINO_MEGA-PadRESET)") (class "Default")
      (node (ref "ARDUINO_MEGA") (pin "RESET") (pinfunction "RESET_RESET") (pintype "bidirectional"))
    )
  )
)
